# filter.net
KiCad netlist of a schematic drawn in Altium Designer
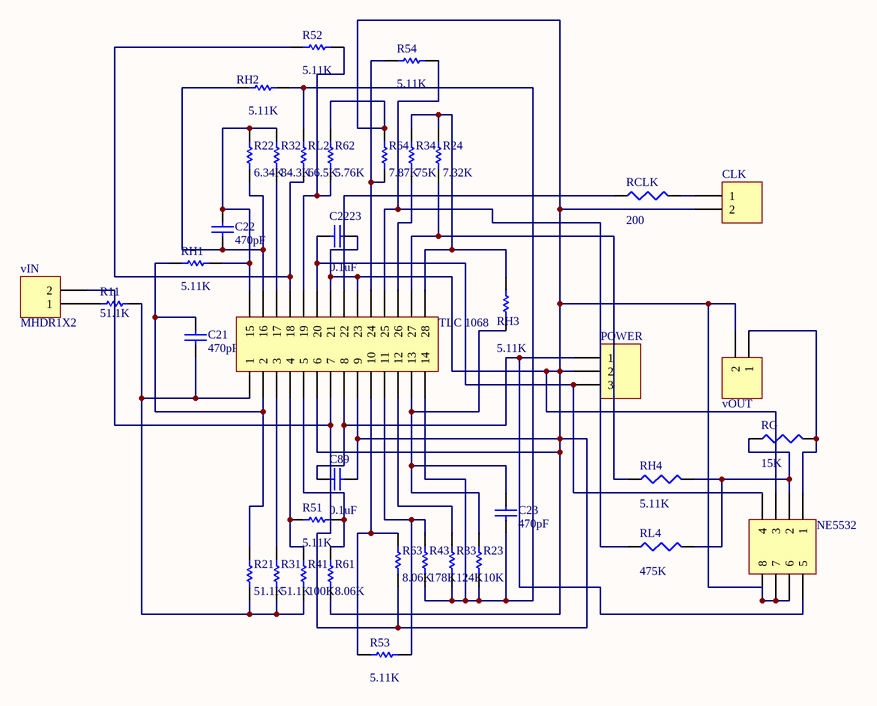
[diagram p0: filter.SchDoc]

(export (version "E")
  (design (tool "Eeschema 10.0.6"))
  (components
    (comp (ref "C21")
      (value "470pF")
      (footprint "RAD-0.3")
      (description "Capacitor")
      (fields (field (name "Comment") "Cap") (field (name "PUBLISHER") "Altium Limited"))
      (libsource (lib "Miscellaneous Devices") (part "Cap"))
    )
    (comp (ref "C22")
      (value "470pF")
      (footprint "RAD-0.3")
      (description "Capacitor")
      (fields (field (name "Comment") "Cap") (field (name "PUBLISHER") "Altium Limited"))
      (libsource (lib "Miscellaneous Devices") (part "Cap"))
    )
    (comp (ref "C23")
      (value "470pF")
      (footprint "RAD-0.3")
      (description "Capacitor")
      (fields (field (name "Comment") "Cap") (field (name "PUBLISHER") "Altium Limited"))
      (libsource (lib "Miscellaneous Devices") (part "Cap"))
    )
    (comp (ref "C89")
      (value "0.1uF")
      (footprint "RAD-0.3")
      (description "Capacitor")
      (fields (field (name "Comment") "Cap") (field (name "PUBLISHER") "Altium Limited"))
      (libsource (lib "Miscellaneous Devices") (part "Cap"))
    )
    (comp (ref "C2223")
      (value "0.1uF")
      (footprint "RAD-0.3")
      (description "Capacitor")
      (fields (field (name "Comment") "Cap") (field (name "PUBLISHER") "Altium Limited"))
      (libsource (lib "Miscellaneous Devices") (part "Cap"))
    )
    (comp (ref "CLK")
      (value "Header 2")
      (footprint "J2")
      (description "Header, 2-Pin")
      (fields (field (name "PUBLISHER") "Altium Limited"))
      (libsource (lib "Miscellaneous Connectors") (part "Header 2"))
    )
    (comp (ref "NE5532")
      (value "Header 4X2A")
      (footprint "J8")
      (description "Header, 4-Pin, Dual row")
      (fields (field (name "PUBLISHER") "Altium Limited"))
      (libsource (lib "Miscellaneous Connectors") (part "Header 4X2A"))
    )
    (comp (ref "POWER")
      (value "Header 3H")
      (footprint "J3")
      (description "Header, 3-Pin, Right Angle")
      (fields (field (name "PUBLISHER") "Altium Limited"))
      (libsource (lib "Miscellaneous Connectors") (part "Header 3H"))
    )
    (comp (ref "R11")
      (value "51.1K")
      (footprint "AXIAL-0.3")
      (description "Resistor")
      (fields (field (name "Comment") "Res1") (field (name "PUBLISHER") "Altium Limited"))
      (libsource (lib "Miscellaneous Devices") (part "Res1"))
    )
    (comp (ref "R21")
      (value "51.1K")
      (footprint "AXIAL-0.3")
      (description "Resistor")
      (fields (field (name "Comment") "Res1") (field (name "PUBLISHER") "Altium Limited"))
      (libsource (lib "Miscellaneous Devices") (part "Res1"))
    )
    (comp (ref "R22")
      (value "6.34K")
      (footprint "AXIAL-0.3")
      (description "Resistor")
      (fields (field (name "Comment") "Res1") (field (name "PUBLISHER") "Altium Limited"))
      (libsource (lib "Miscellaneous Devices") (part "Res1"))
    )
    (comp (ref "R23")
      (value "10K")
      (footprint "AXIAL-0.3")
      (description "Resistor")
      (fields (field (name "Comment") "Res1") (field (name "PUBLISHER") "Altium Limited"))
      (libsource (lib "Miscellaneous Devices") (part "Res1"))
    )
    (comp (ref "R24")
      (value "7.32K")
      (footprint "AXIAL-0.3")
      (description "Resistor")
      (fields (field (name "Comment") "Res1") (field (name "PUBLISHER") "Altium Limited"))
      (libsource (lib "Miscellaneous Devices") (part "Res1"))
    )
    (comp (ref "R31")
      (value "51.1K")
      (footprint "AXIAL-0.3")
      (description "Resistor")
      (fields (field (name "Comment") "Res1") (field (name "PUBLISHER") "Altium Limited"))
      (libsource (lib "Miscellaneous Devices") (part "Res1"))
    )
    (comp (ref "R32")
      (value "84.3K")
      (footprint "AXIAL-0.3")
      (description "Resistor")
      (fields (field (name "Comment") "Res1") (field (name "PUBLISHER") "Altium Limited"))
      (libsource (lib "Miscellaneous Devices") (part "Res1"))
    )
    (comp (ref "R33")
      (value "124K")
      (footprint "AXIAL-0.3")
      (description "Resistor")
      (fields (field (name "Comment") "Res1") (field (name "PUBLISHER") "Altium Limited"))
      (libsource (lib "Miscellaneous Devices") (part "Res1"))
    )
    (comp (ref "R34")
      (value "75K")
      (footprint "AXIAL-0.3")
      (description "Resistor")
      (fields (field (name "Comment") "Res1") (field (name "PUBLISHER") "Altium Limited"))
      (libsource (lib "Miscellaneous Devices") (part "Res1"))
    )
    (comp (ref "R41")
      (value "100K")
      (footprint "AXIAL-0.3")
      (description "Resistor")
      (fields (field (name "Comment") "Res1") (field (name "PUBLISHER") "Altium Limited"))
      (libsource (lib "Miscellaneous Devices") (part "Res1"))
    )
    (comp (ref "R43")
      (value "178K")
      (footprint "AXIAL-0.3")
      (description "Resistor")
      (fields (field (name "Comment") "Res1") (field (name "PUBLISHER") "Altium Limited"))
      (libsource (lib "Miscellaneous Devices") (part "Res1"))
    )
    (comp (ref "R51")
      (value "5.11K")
      (footprint "AXIAL-0.3")
      (description "Resistor")
      (fields (field (name "Comment") "Res1") (field (name "PUBLISHER") "Altium Limited"))
      (libsource (lib "Miscellaneous Devices") (part "Res1"))
    )
    (comp (ref "R52")
      (value "5.11K")
      (footprint "AXIAL-0.3")
      (description "Resistor")
      (fields (field (name "Comment") "Res1") (field (name "PUBLISHER") "Altium Limited"))
      (libsource (lib "Miscellaneous Devices") (part "Res1"))
    )
    (comp (ref "R53")
      (value "5.11K")
      (footprint "AXIAL-0.3")
      (description "Resistor")
      (fields (field (name "Comment") "Res1") (field (name "PUBLISHER") "Altium Limited"))
      (libsource (lib "Miscellaneous Devices") (part "Res1"))
    )
    (comp (ref "R54")
      (value "5.11K")
      (footprint "AXIAL-0.3")
      (description "Resistor")
      (fields (field (name "Comment") "Res1") (field (name "PUBLISHER") "Altium Limited"))
      (libsource (lib "Miscellaneous Devices") (part "Res1"))
    )
    (comp (ref "R61")
      (value "8.06K")
      (footprint "AXIAL-0.3")
      (description "Resistor")
      (fields (field (name "Comment") "Res1") (field (name "PUBLISHER") "Altium Limited"))
      (libsource (lib "Miscellaneous Devices") (part "Res1"))
    )
    (comp (ref "R62")
      (value "5.76K")
      (footprint "AXIAL-0.3")
      (description "Resistor")
      (fields (field (name "Comment") "Res1") (field (name "PUBLISHER") "Altium Limited"))
      (libsource (lib "Miscellaneous Devices") (part "Res1"))
    )
    (comp (ref "R63")
      (value "8.06K")
      (footprint "AXIAL-0.3")
      (description "Resistor")
      (fields (field (name "Comment") "Res1") (field (name "PUBLISHER") "Altium Limited"))
      (libsource (lib "Miscellaneous Devices") (part "Res1"))
    )
    (comp (ref "R64")
      (value "7.87K")
      (footprint "AXIAL-0.3")
      (description "Resistor")
      (fields (field (name "Comment") "Res1") (field (name "PUBLISHER") "Altium Limited"))
      (libsource (lib "Miscellaneous Devices") (part "Res1"))
    )
    (comp (ref "RCLK")
      (value "200")
      (footprint "AXIAL-0.3")
      (description "Resistor")
      (fields (field (name "Comment") "RCLK") (field (name "PUBLISHER") "Altium Limited"))
      (libsource (lib "Miscellaneous Devices") (part "Res3"))
    )
    (comp (ref "RG")
      (value "15K")
      (footprint "AXIAL-0.3")
      (description "Resistor")
      (fields (field (name "Comment") "Res3") (field (name "PUBLISHER") "Altium Limited"))
      (libsource (lib "Miscellaneous Devices") (part "Res3"))
    )
    (comp (ref "RH1")
      (value "5.11K")
      (footprint "AXIAL-0.3")
      (description "Resistor")
      (fields (field (name "Comment") "Res1") (field (name "PUBLISHER") "Altium Limited"))
      (libsource (lib "Miscellaneous Devices") (part "Res1"))
    )
    (comp (ref "RH2")
      (value "5.11K")
      (footprint "AXIAL-0.3")
      (description "Resistor")
      (fields (field (name "Comment") "Res1") (field (name "PUBLISHER") "Altium Limited"))
      (libsource (lib "Miscellaneous Devices") (part "Res1"))
    )
    (comp (ref "RH3")
      (value "5.11K")
      (footprint "AXIAL-0.3")
      (description "Resistor")
      (fields (field (name "Comment") "Res1") (field (name "PUBLISHER") "Altium Limited"))
      (libsource (lib "Miscellaneous Devices") (part "Res1"))
    )
    (comp (ref "RH4")
      (value "5.11K")
      (footprint "AXIAL-0.3")
      (description "Resistor")
      (fields (field (name "Comment") "Res3") (field (name "PUBLISHER") "Altium Limited"))
      (libsource (lib "Miscellaneous Devices") (part "Res3"))
    )
    (comp (ref "RL2")
      (value "66.5K")
      (footprint "AXIAL-0.3")
      (description "Resistor")
      (fields (field (name "Comment") "Res1") (field (name "PUBLISHER") "Altium Limited"))
      (libsource (lib "Miscellaneous Devices") (part "Res1"))
    )
    (comp (ref "RL4")
      (value "475K")
      (footprint "AXIAL-0.3")
      (description "Resistor")
      (fields (field (name "Comment") "Res3") (field (name "PUBLISHER") "Altium Limited"))
      (libsource (lib "Miscellaneous Devices") (part "Res3"))
    )
    (comp (ref "TLC 1068")
      (value "Header 14X2A")
      (footprint "J28")
      (description "Header, 14-Pin, Dual row")
      (fields (field (name "PUBLISHER") "Altium Limited"))
      (libsource (lib "Miscellaneous Connectors") (part "Header 14X2A"))
    )
    (comp (ref "vIN")
      (value "MHDR1X2")
      (footprint "J2")
      (description "Header, 2-Pin")
      (fields (field (name "PUBLISHER") "Altium Limited"))
      (libsource (lib "Miscellaneous Connectors") (part "MHDR1X2"))
    )
    (comp (ref "vOUT")
      (value "MHDR1X2")
      (footprint "J2")
      (description "Header, 2-Pin")
      (fields (field (name "PUBLISHER") "Altium Limited"))
      (libsource (lib "") (part "MHDR1X2_1"))
    )
  )
  (nets
    (net (code "1") (name "Net-(C21-Pad1)") (class "Default")
      (node (ref "C21") (pin "1") (pinfunction "1_1") (pintype "passive"))
      (node (ref "R11") (pin "1") (pinfunction "1_1") (pintype "passive"))
      (node (ref "R21") (pin "1") (pinfunction "1_1") (pintype "passive"))
      (node (ref "R31") (pin "1") (pinfunction "1_1") (pintype "passive"))
      (node (ref "R41") (pin "1") (pinfunction "1_1") (pintype "passive"))
      (node (ref "TLC 1068") (pin "1") (pinfunction "1_1") (pintype "passive"))
    )
    (net (code "2") (name "Net-(C21-Pad2)") (class "Default")
      (node (ref "C21") (pin "2") (pinfunction "2_2") (pintype "passive"))
      (node (ref "R21") (pin "2") (pinfunction "2_2") (pintype "passive"))
      (node (ref "RH1") (pin "2") (pinfunction "2_2") (pintype "passive"))
      (node (ref "TLC 1068") (pin "2") (pinfunction "2_2") (pintype "passive"))
    )
    (net (code "3") (name "Net-(C22-Pad1)") (class "Default")
      (node (ref "C22") (pin "1") (pinfunction "1_1") (pintype "passive"))
      (node (ref "R22") (pin "1") (pinfunction "1_1") (pintype "passive"))
      (node (ref "RH2") (pin "1") (pinfunction "1_1") (pintype "passive"))
      (node (ref "TLC 1068") (pin "16") (pinfunction "16_16") (pintype "passive"))
    )
    (net (code "4") (name "Net-(C22-Pad2)") (class "Default")
      (node (ref "C22") (pin "2") (pinfunction "2_2") (pintype "passive"))
      (node (ref "R22") (pin "2") (pinfunction "2_2") (pintype "passive"))
      (node (ref "R32") (pin "2") (pinfunction "2_2") (pintype "passive"))
      (node (ref "RH1") (pin "1") (pinfunction "1_1") (pintype "passive"))
      (node (ref "TLC 1068") (pin "15") (pinfunction "15_15") (pintype "passive"))
    )
    (net (code "5") (name "Net-(C23-Pad1)") (class "Default")
      (node (ref "C23") (pin "1") (pinfunction "1_1") (pintype "passive"))
      (node (ref "R23") (pin "1") (pinfunction "1_1") (pintype "passive"))
      (node (ref "R33") (pin "1") (pinfunction "1_1") (pintype "passive"))
      (node (ref "R43") (pin "1") (pinfunction "1_1") (pintype "passive"))
      (node (ref "RH2") (pin "2") (pinfunction "2_2") (pintype "passive"))
      (node (ref "RL2") (pin "2") (pinfunction "2_2") (pintype "passive"))
      (node (ref "TLC 1068") (pin "14") (pinfunction "14_14") (pintype "passive"))
    )
    (net (code "6") (name "Net-(C23-Pad2)") (class "Default")
      (node (ref "C23") (pin "2") (pinfunction "2_2") (pintype "passive"))
      (node (ref "R23") (pin "2") (pinfunction "2_2") (pintype "passive"))
      (node (ref "RH3") (pin "1") (pinfunction "1_1") (pintype "passive"))
      (node (ref "TLC 1068") (pin "13") (pinfunction "13_13") (pintype "passive"))
    )
    (net (code "7") (name "Net-(C89-Pad1)") (class "Default")
      (node (ref "C89") (pin "1") (pinfunction "1_1") (pintype "passive"))
      (node (ref "NE5532") (pin "5") (pinfunction "5_5") (pintype "passive"))
      (node (ref "POWER") (pin "1") (pinfunction "1_1") (pintype "passive"))
      (node (ref "TLC 1068") (pin "8") (pinfunction "8_8") (pintype "passive"))
    )
    (net (code "8") (name "Net-(C2223-Pad1)") (class "Default")
      (node (ref "C2223") (pin "1") (pinfunction "1_1") (pintype "passive"))
      (node (ref "NE5532") (pin "4") (pinfunction "4_4") (pintype "passive"))
      (node (ref "POWER") (pin "3") (pinfunction "3_3") (pintype "passive"))
      (node (ref "TLC 1068") (pin "20") (pinfunction "20_20") (pintype "passive"))
    )
    (net (code "9") (name "Net-(C2223-Pad2)") (class "Default")
      (node (ref "C2223") (pin "2") (pinfunction "2_2") (pintype "passive"))
      (node (ref "C89") (pin "2") (pinfunction "2_2") (pintype "passive"))
      (node (ref "CLK") (pin "2") (pinfunction "2_2") (pintype "passive"))
      (node (ref "NE5532") (pin "3") (pinfunction "3_3") (pintype "passive"))
      (node (ref "NE5532") (pin "6") (pinfunction "6_6") (pintype "passive"))
      (node (ref "NE5532") (pin "7") (pinfunction "7_7") (pintype "passive"))
      (node (ref "NE5532") (pin "8") (pinfunction "8_8") (pintype "passive"))
      (node (ref "POWER") (pin "2") (pinfunction "2_2") (pintype "passive"))
      (node (ref "R61") (pin "1") (pinfunction "1_1") (pintype "passive"))
      (node (ref "R62") (pin "2") (pinfunction "2_2") (pintype "passive"))
      (node (ref "R63") (pin "1") (pinfunction "1_1") (pintype "passive"))
      (node (ref "R64") (pin "2") (pinfunction "2_2") (pintype "passive"))
      (node (ref "TLC 1068") (pin "21") (pinfunction "21_21") (pintype "passive"))
      (node (ref "TLC 1068") (pin "23") (pinfunction "23_23") (pintype "passive"))
      (node (ref "TLC 1068") (pin "6") (pinfunction "6_6") (pintype "passive"))
      (node (ref "TLC 1068") (pin "7") (pinfunction "7_7") (pintype "passive"))
      (node (ref "TLC 1068") (pin "9") (pinfunction "9_9") (pintype "passive"))
      (node (ref "vIN") (pin "2") (pinfunction "2_2") (pintype "passive"))
      (node (ref "vOUT") (pin "2") (pinfunction "2_2") (pintype "passive"))
    )
    (net (code "10") (name "Net-(CLK-Pad1)") (class "Default")
      (node (ref "CLK") (pin "1") (pinfunction "1_1") (pintype "passive"))
      (node (ref "RCLK") (pin "2") (pinfunction "2_2") (pintype "passive"))
    )
    (net (code "11") (name "Net-(NE5532-Pad1)") (class "Default")
      (node (ref "NE5532") (pin "1") (pinfunction "1_1") (pintype "passive"))
      (node (ref "RG") (pin "2") (pinfunction "2_2") (pintype "passive"))
      (node (ref "vOUT") (pin "1") (pinfunction "1_1") (pintype "passive"))
    )
    (net (code "12") (name "Net-(NE5532-Pad2)") (class "Default")
      (node (ref "NE5532") (pin "2") (pinfunction "2_2") (pintype "passive"))
      (node (ref "RG") (pin "1") (pinfunction "1_1") (pintype "passive"))
      (node (ref "RH4") (pin "2") (pinfunction "2_2") (pintype "passive"))
      (node (ref "RL4") (pin "2") (pinfunction "2_2") (pintype "passive"))
    )
    (net (code "13") (name "Net-(R11-Pad2)") (class "Default")
      (node (ref "R11") (pin "2") (pinfunction "2_2") (pintype "passive"))
      (node (ref "vIN") (pin "1") (pinfunction "1_1") (pintype "passive"))
    )
    (net (code "14") (name "Net-(R24-Pad1)") (class "Default")
      (node (ref "R24") (pin "1") (pinfunction "1_1") (pintype "passive"))
      (node (ref "RH4") (pin "1") (pinfunction "1_1") (pintype "passive"))
      (node (ref "TLC 1068") (pin "27") (pinfunction "27_27") (pintype "passive"))
    )
    (net (code "15") (name "Net-(R24-Pad2)") (class "Default")
      (node (ref "R24") (pin "2") (pinfunction "2_2") (pintype "passive"))
      (node (ref "R34") (pin "2") (pinfunction "2_2") (pintype "passive"))
      (node (ref "RH3") (pin "2") (pinfunction "2_2") (pintype "passive"))
      (node (ref "TLC 1068") (pin "28") (pinfunction "28_28") (pintype "passive"))
    )
    (net (code "16") (name "Net-(R31-Pad2)") (class "Default")
      (node (ref "R31") (pin "2") (pinfunction "2_2") (pintype "passive"))
      (node (ref "TLC 1068") (pin "3") (pinfunction "3_3") (pintype "passive"))
    )
    (net (code "17") (name "Net-(R32-Pad1)") (class "Default")
      (node (ref "R32") (pin "1") (pinfunction "1_1") (pintype "passive"))
      (node (ref "TLC 1068") (pin "17") (pinfunction "17_17") (pintype "passive"))
    )
    (net (code "18") (name "Net-(R33-Pad2)") (class "Default")
      (node (ref "R33") (pin "2") (pinfunction "2_2") (pintype "passive"))
      (node (ref "TLC 1068") (pin "12") (pinfunction "12_12") (pintype "passive"))
    )
    (net (code "19") (name "Net-(R34-Pad1)") (class "Default")
      (node (ref "R34") (pin "1") (pinfunction "1_1") (pintype "passive"))
      (node (ref "TLC 1068") (pin "26") (pinfunction "26_26") (pintype "passive"))
    )
    (net (code "20") (name "Net-(R41-Pad2)") (class "Default")
      (node (ref "R41") (pin "2") (pinfunction "2_2") (pintype "passive"))
      (node (ref "R51") (pin "1") (pinfunction "1_1") (pintype "passive"))
      (node (ref "TLC 1068") (pin "4") (pinfunction "4_4") (pintype "passive"))
    )
    (net (code "21") (name "Net-(R43-Pad2)") (class "Default")
      (node (ref "R43") (pin "2") (pinfunction "2_2") (pintype "passive"))
      (node (ref "R53") (pin "2") (pinfunction "2_2") (pintype "passive"))
      (node (ref "TLC 1068") (pin "11") (pinfunction "11_11") (pintype "passive"))
    )
    (net (code "22") (name "Net-(R51-Pad2)") (class "Default")
      (node (ref "R51") (pin "2") (pinfunction "2_2") (pintype "passive"))
      (node (ref "R61") (pin "2") (pinfunction "2_2") (pintype "passive"))
      (node (ref "TLC 1068") (pin "5") (pinfunction "5_5") (pintype "passive"))
    )
    (net (code "23") (name "Net-(R52-Pad1)") (class "Default")
      (node (ref "R52") (pin "1") (pinfunction "1_1") (pintype "passive"))
      (node (ref "RL2") (pin "1") (pinfunction "1_1") (pintype "passive"))
      (node (ref "TLC 1068") (pin "18") (pinfunction "18_18") (pintype "passive"))
    )
    (net (code "24") (name "Net-(R52-Pad2)") (class "Default")
      (node (ref "R52") (pin "2") (pinfunction "2_2") (pintype "passive"))
      (node (ref "R62") (pin "1") (pinfunction "1_1") (pintype "passive"))
      (node (ref "TLC 1068") (pin "19") (pinfunction "19_19") (pintype "passive"))
    )
    (net (code "25") (name "Net-(R53-Pad1)") (class "Default")
      (node (ref "R53") (pin "1") (pinfunction "1_1") (pintype "passive"))
      (node (ref "R63") (pin "2") (pinfunction "2_2") (pintype "passive"))
      (node (ref "TLC 1068") (pin "10") (pinfunction "10_10") (pintype "passive"))
    )
    (net (code "26") (name "Net-(R54-Pad1)") (class "Default")
      (node (ref "R54") (pin "1") (pinfunction "1_1") (pintype "passive"))
      (node (ref "RL4") (pin "1") (pinfunction "1_1") (pintype "passive"))
      (node (ref "TLC 1068") (pin "25") (pinfunction "25_25") (pintype "passive"))
    )
    (net (code "27") (name "Net-(R54-Pad2)") (class "Default")
      (node (ref "R54") (pin "2") (pinfunction "2_2") (pintype "passive"))
      (node (ref "R64") (pin "1") (pinfunction "1_1") (pintype "passive"))
      (node (ref "TLC 1068") (pin "24") (pinfunction "24_24") (pintype "passive"))
    )
    (net (code "28") (name "Net-(RCLK-Pad1)") (class "Default")
      (node (ref "RCLK") (pin "1") (pinfunction "1_1") (pintype "passive"))
      (node (ref "TLC 1068") (pin "22") (pinfunction "22_22") (pintype "passive"))
    )
  )
)
